# 2-Electrovalves.net
KiCad netlist of a schematic drawn in Altium Designer
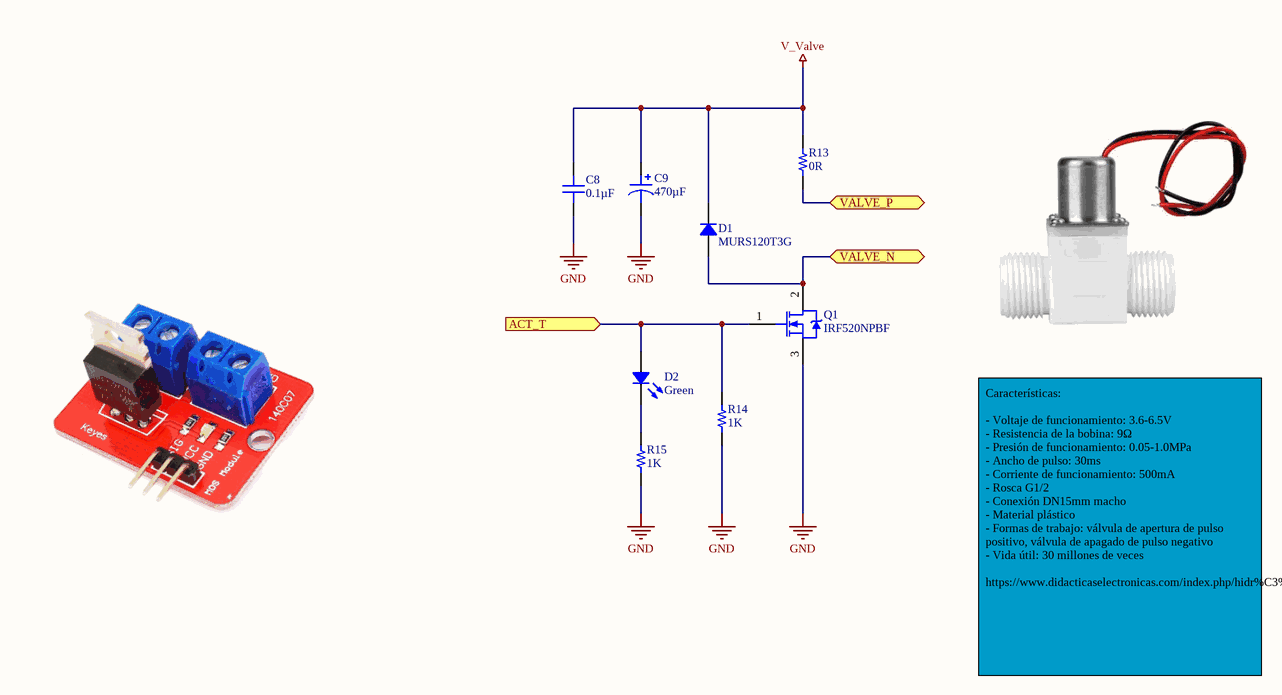
[diagram p0: 2-Electrovalves.SchDoc]

(export (version "E")
  (design (tool "Eeschema 10.0.6"))
  (components
    (comp (ref "C8")
      (value "0.1µF")
      (footprint "CAP 0805_2012")
      (description "CAP CER 0.1UF 50V X7R 0805")
      (fields (field (name "PART NUMBER") "C0805C104M5RACAUTO") (field (name "MANUFACTURER") "KEMET"))
      (libsource (lib "Celestial Altium Library - altium_library") (part "Capacitor"))
    )
    (comp (ref "C9")
      (value "470µF")
      (footprint "CAP TH ALUM ELEC D10.00mm S5.00mm H14.50mm")
      (description "CAP ALUM 47UF 20% 63V RADIAL")
      (fields
        (field (name "PART NUMBER") "UBT1J470MPD1TD")
        (field (name "MANUFACTURER") "Nichicon")
        (field (name "LASTUPDATED") "2/09/2020 1:31:15 a. m.")
      )
      (libsource (lib "Celestial Altium Library - altium_library") (part "Polarised Capacitor"))
    )
    (comp (ref "D1")
      (value "MURS120T3G")
      (footprint "DO214AA SMB")
      (description "DIODE GEN PURP 200V 2A SMB")
      (fields
        (field (name "MANUFACTURER") "ON Semiconductor")
        (field (name "LASTUPDATED") "12/04/2022 10:48:18 p. m.")
      )
      (libsource (lib "Celestial Altium Library - altium_library") (part "Diode"))
    )
    (comp (ref "D2")
      (value "Green")
      (footprint "LED 0805_2012 YELLOW")
      (description "LED YELLOW CLEAR CHIP SMD")
      (fields
        (field (name "PART NUMBER") "APT2012SYCK")
        (field (name "MANUFACTURER") "Kingbright")
        (field (name "LASTUPDATED") "12/04/2022 10:52:50 p. m.")
      )
      (libsource (lib "Celestial Altium Library - altium_library") (part "LED"))
    )
    (comp (ref "Q1")
      (value "IRF520NPBF")
      (footprint "INTR-TO-220AB-3")
      (description "HEXFET(R) Power MOSFET, 100 V, 9.7 A, 0.2 Ohm, -55 to 175 degC, 3-Pin FM (TO-220AB), RoHS, Tube")
      (fields (field (name "MANUFACTURER") "International Rectifier"))
      (libsource (lib "Altium Content Vault") (part "NEMOS-GDS-3_B"))
    )
    (comp (ref "R13")
      (value "0R")
      (footprint "RES 0805_2012")
      (description "RES SMD 1.47K OHM 1% 1/8W 0805")
      (fields (field (name "PART NUMBER") "RC0805FR-071K47L") (field (name "MANUFACTURER") "Yageo"))
      (libsource (lib "Celestial Altium Library - altium_library") (part "Resistor"))
    )
    (comp (ref "R14")
      (value "1K")
      (footprint "RES 0805_2012")
      (description "RES SMD 1.47K OHM 1% 1/8W 0805")
      (fields (field (name "PART NUMBER") "RC0805FR-071K47L") (field (name "MANUFACTURER") "Yageo"))
      (libsource (lib "Celestial Altium Library - altium_library") (part "Resistor"))
    )
    (comp (ref "R15")
      (value "1K")
      (footprint "RES 0805_2012")
      (description "RES SMD 1.47K OHM 1% 1/8W 0805")
      (fields (field (name "PART NUMBER") "RC0805FR-071K47L") (field (name "MANUFACTURER") "Yageo"))
      (libsource (lib "Celestial Altium Library - altium_library") (part "Resistor"))
    )
  )
  (nets
    (net (code "1") (name "/ACT_T") (class "Default")
      (node (ref "D2") (pin "1") (pinfunction "1_1") (pintype "passive"))
      (node (ref "Q1") (pin "1") (pinfunction "G_1") (pintype "passive"))
      (node (ref "R14") (pin "2") (pinfunction "2_2") (pintype "passive"))
    )
    (net (code "2") (name "/VALVE_N") (class "Default")
      (node (ref "D1") (pin "1") (pinfunction "1_1") (pintype "passive"))
      (node (ref "Q1") (pin "2") (pinfunction "D_2") (pintype "passive"))
    )
    (net (code "3") (name "/VALVE_P") (class "Default")
      (node (ref "R13") (pin "1") (pinfunction "1_1") (pintype "passive"))
    )
    (net (code "4") (name "GND") (class "Default")
      (node (ref "C8") (pin "1") (pinfunction "1_1") (pintype "passive"))
      (node (ref "C9") (pin "2") (pinfunction "2_2") (pintype "passive"))
      (node (ref "Q1") (pin "3") (pinfunction "S_3") (pintype "passive"))
      (node (ref "R14") (pin "1") (pinfunction "1_1") (pintype "passive"))
      (node (ref "R15") (pin "1") (pinfunction "1_1") (pintype "passive"))
    )
    (net (code "5") (name "Net-(D2-Pad2)") (class "Default")
      (node (ref "D2") (pin "2") (pinfunction "2_2") (pintype "passive"))
      (node (ref "R15") (pin "2") (pinfunction "2_2") (pintype "passive"))
    )
    (net (code "6") (name "V_Valve") (class "Default")
      (node (ref "C8") (pin "2") (pinfunction "2_2") (pintype "passive"))
      (node (ref "C9") (pin "1") (pinfunction "1_1") (pintype "passive"))
      (node (ref "D1") (pin "2") (pinfunction "2_2") (pintype "passive"))
      (node (ref "R13") (pin "2") (pinfunction "2_2") (pintype "passive"))
    )
  )
)
